# spi_rom.net
KiCad netlist of a schematic drawn in EAGLE
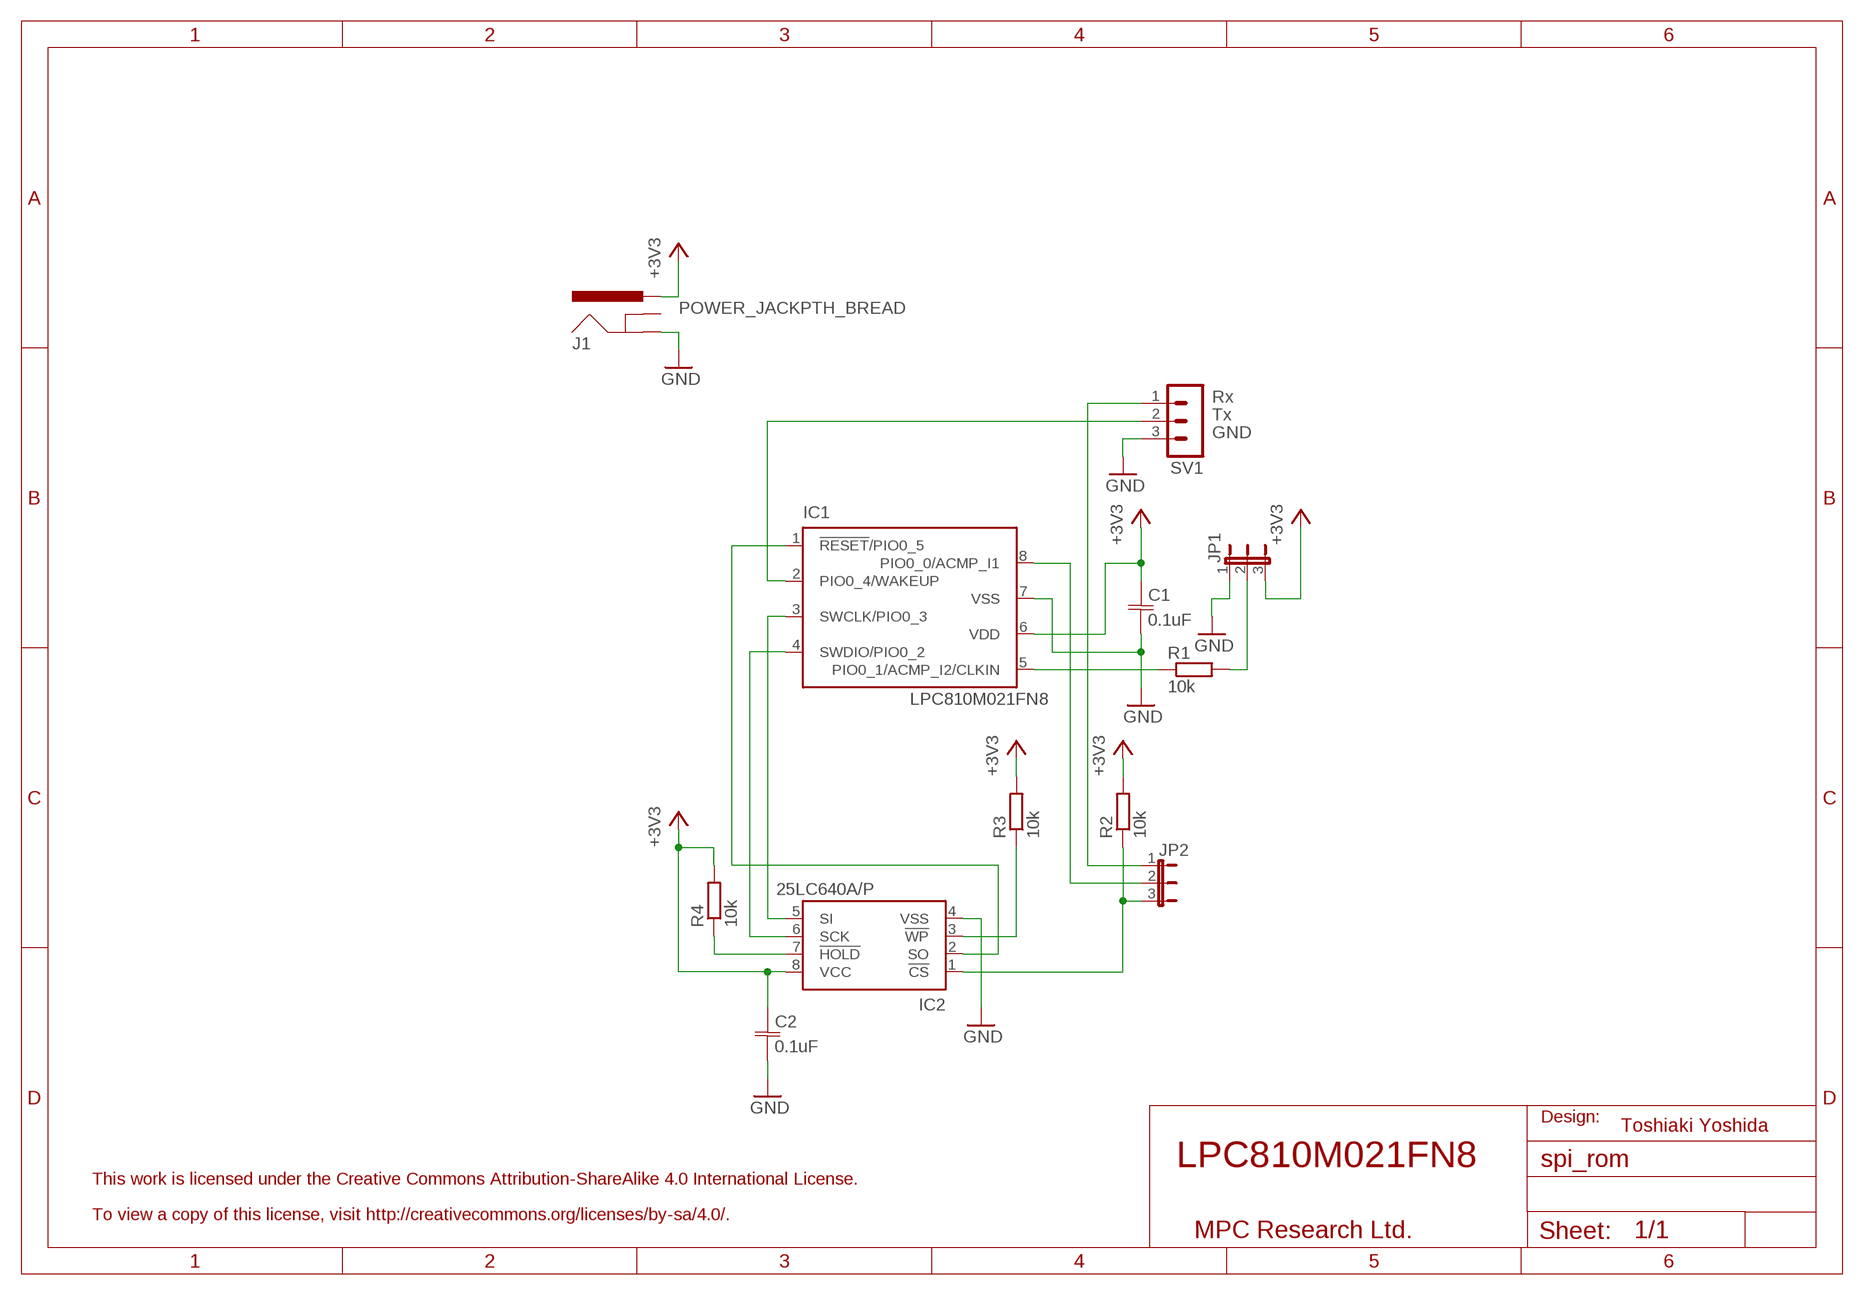
[diagram p0: schematic, sheet 1]

(export (version "E")
  (design (tool "Eeschema 10.0.6"))
  (components
    (comp (ref "C1")
      (value "0.1uF")
      (footprint "eagle-import:C050-024X044")
      (libsource (lib "eagle-import") (part "C-JIS050-024X044"))
    )
    (comp (ref "C2")
      (value "0.1uF")
      (footprint "eagle-import:C050-024X044")
      (libsource (lib "eagle-import") (part "C-JIS050-024X044"))
    )
    (comp (ref "IC1")
      (value "LPC810M021FN8")
      (footprint "eagle-import:DIL08")
      (libsource (lib "eagle-import") (part "LPC810M021FN8"))
    )
    (comp (ref "IC2")
      (value "25LC640A/P")
      (footprint "eagle-import:DIL8")
      (libsource (lib "eagle-import") (part "25/PLC640A"))
    )
    (comp (ref "J1")
      (value "POWER_JACKPTH_BREAD")
      (footprint "eagle-import:POWER_JACK_PTH_BREAD")
      (libsource (lib "eagle-import") (part "POWER_JACKPTH_BREAD"))
    )
    (comp (ref "JP1")
      (value "JP2E")
      (footprint "eagle-import:JP2")
      (libsource (lib "eagle-import") (part "JP2E"))
    )
    (comp (ref "JP2")
      (value "JP2E")
      (footprint "eagle-import:JP2")
      (libsource (lib "eagle-import") (part "JP2E"))
    )
    (comp (ref "R1")
      (value "10k")
      (footprint "eagle-import:0207_10")
      (libsource (lib "eagle-import") (part "R-EU_0207/10"))
    )
    (comp (ref "R2")
      (value "10k")
      (footprint "eagle-import:0207_10")
      (libsource (lib "eagle-import") (part "R-EU_0207/10"))
    )
    (comp (ref "R3")
      (value "10k")
      (footprint "eagle-import:0207_10")
      (libsource (lib "eagle-import") (part "R-EU_0207/10"))
    )
    (comp (ref "R4")
      (value "10k")
      (footprint "eagle-import:0207_10")
      (libsource (lib "eagle-import") (part "R-EU_0207/10"))
    )
    (comp (ref "SV1")
      (value "MA03-1")
      (footprint "eagle-import:MA03-1")
      (libsource (lib "eagle-import") (part "MA03-1"))
    )
  )
  (nets
    (net (code "1") (name "+3V3") (class "Default")
      (node (ref "C1") (pin "1") (pinfunction "1_1") (pintype "passive"))
      (node (ref "C2") (pin "1") (pinfunction "1_1") (pintype "passive"))
      (node (ref "IC1") (pin "6") (pinfunction "VDD_6") (pintype "power_in"))
      (node (ref "IC2") (pin "8") (pinfunction "VCC_8") (pintype "power_in"))
      (node (ref "J1") (pin "PWR") (pinfunction "PWR_PWR") (pintype "bidirectional"))
      (node (ref "JP1") (pin "3") (pinfunction "3_3") (pintype "passive"))
      (node (ref "R2") (pin "2") (pinfunction "2_2") (pintype "passive"))
      (node (ref "R3") (pin "2") (pinfunction "2_2") (pintype "passive"))
      (node (ref "R4") (pin "2") (pinfunction "2_2") (pintype "passive"))
    )
    (net (code "2") (name "GND") (class "Default")
      (node (ref "C1") (pin "2") (pinfunction "2_2") (pintype "passive"))
      (node (ref "C2") (pin "2") (pinfunction "2_2") (pintype "passive"))
      (node (ref "IC1") (pin "7") (pinfunction "VSS_7") (pintype "power_in"))
      (node (ref "IC2") (pin "4") (pinfunction "VSS_4") (pintype "power_in"))
      (node (ref "J1") (pin "GND") (pinfunction "GND_GND") (pintype "bidirectional"))
      (node (ref "JP1") (pin "1") (pinfunction "1_1") (pintype "passive"))
      (node (ref "SV1") (pin "3") (pinfunction "3_3") (pintype "passive"))
    )
    (net (code "3") (name "Net-(IC1-PIO0_0{slash}ACMP_I1)") (class "Default")
      (node (ref "IC1") (pin "8") (pinfunction "PIO0_0/ACMP_I1_8") (pintype "bidirectional"))
      (node (ref "JP2") (pin "2") (pinfunction "2_2") (pintype "passive"))
    )
    (net (code "4") (name "Net-(IC1-PIO0_1{slash}ACMP_I2{slash}CLKIN)") (class "Default")
      (node (ref "IC1") (pin "5") (pinfunction "PIO0_1/ACMP_I2/CLKIN_5") (pintype "bidirectional"))
      (node (ref "R1") (pin "1") (pinfunction "1_1") (pintype "passive"))
    )
    (net (code "5") (name "Net-(IC1-PIO0_4{slash}WAKEUP)") (class "Default")
      (node (ref "IC1") (pin "2") (pinfunction "PIO0_4/WAKEUP_2") (pintype "bidirectional"))
      (node (ref "SV1") (pin "2") (pinfunction "2_2") (pintype "passive"))
    )
    (net (code "6") (name "Net-(IC1-SWCLK{slash}PIO0_3)") (class "Default")
      (node (ref "IC1") (pin "3") (pinfunction "SWCLK/PIO0_3_3") (pintype "bidirectional"))
      (node (ref "IC2") (pin "5") (pinfunction "SI_5") (pintype "input"))
    )
    (net (code "7") (name "Net-(IC1-SWDIO{slash}PIO0_2)") (class "Default")
      (node (ref "IC1") (pin "4") (pinfunction "SWDIO/PIO0_2_4") (pintype "bidirectional"))
      (node (ref "IC2") (pin "6") (pinfunction "SCK_6") (pintype "input"))
    )
    (net (code "8") (name "Net-(IC1-~{RESET}{slash}PIO0_5)") (class "Default")
      (node (ref "IC1") (pin "1") (pinfunction "~{RESET}/PIO0_5_1") (pintype "bidirectional"))
      (node (ref "IC2") (pin "2") (pinfunction "SO_2") (pintype "output"))
    )
    (net (code "9") (name "Net-(IC2-~{CS})") (class "Default")
      (node (ref "IC2") (pin "1") (pinfunction "~{CS}_1") (pintype "input"))
      (node (ref "JP2") (pin "3") (pinfunction "3_3") (pintype "passive"))
      (node (ref "R2") (pin "1") (pinfunction "1_1") (pintype "passive"))
    )
    (net (code "10") (name "Net-(IC2-~{HOLD})") (class "Default")
      (node (ref "IC2") (pin "7") (pinfunction "~{HOLD}_7") (pintype "input"))
      (node (ref "R4") (pin "1") (pinfunction "1_1") (pintype "passive"))
    )
    (net (code "11") (name "Net-(IC2-~{WP})") (class "Default")
      (node (ref "IC2") (pin "3") (pinfunction "~{WP}_3") (pintype "input"))
      (node (ref "R3") (pin "1") (pinfunction "1_1") (pintype "passive"))
    )
    (net (code "12") (name "Net-(JP1-Pad2)") (class "Default")
      (node (ref "JP1") (pin "2") (pinfunction "2_2") (pintype "passive"))
      (node (ref "R1") (pin "2") (pinfunction "2_2") (pintype "passive"))
    )
    (net (code "13") (name "Net-(JP2-Pad1)") (class "Default")
      (node (ref "JP2") (pin "1") (pinfunction "1_1") (pintype "passive"))
      (node (ref "SV1") (pin "1") (pinfunction "1_1") (pintype "passive"))
    )
    (net (code "14") (name "unconnected-(J1-PadGNDBREAK)") (class "Default")
      (node (ref "J1") (pin "GNDBREAK") (pinfunction "GNDBREAK_GNDBREAK") (pintype "bidirectional"))
    )
  )
)
